# BatteryMonitor-12V-LMT2901.net
KiCad netlist of a schematic drawn in EAGLE
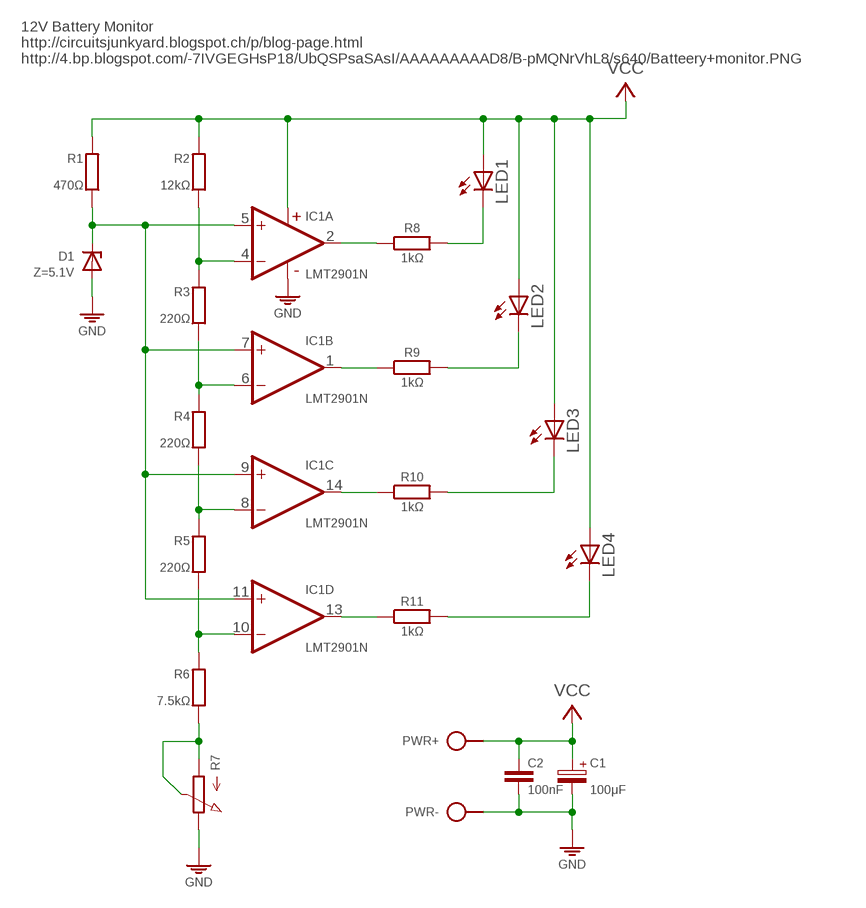
[diagram p0: schematic, sheet 1]

(export (version "E")
  (design (tool "Eeschema 10.0.6"))
  (components
    (comp (ref "C1")
      (value "100μF")
      (footprint "eagle-import:E2,5-4")
      (libsource (lib "eagle-import") (part "CPOLE2,5-4"))
    )
    (comp (ref "C2")
      (value "100nF")
      (footprint "eagle-import:C050-020X044")
      (libsource (lib "eagle-import") (part "C050-020X044"))
    )
    (comp (ref "D1")
      (value "Z=5.1V")
      (footprint "eagle-import:DO34Z5V")
      (libsource (lib "eagle-import") (part "Z-DIODE34Z5V"))
    )
    (comp (ref "IC1")
      (value "LMT2901N")
      (footprint "eagle-import:DIL14")
      (libsource (lib "eagle-import") (part "LMT2901N"))
    )
    (comp (ref "LED1")
      (value "LED3MM")
      (footprint "eagle-import:LED3MM")
      (libsource (lib "eagle-import") (part "LED3MM"))
    )
    (comp (ref "LED2")
      (value "LED3MM")
      (footprint "eagle-import:LED3MM")
      (libsource (lib "eagle-import") (part "LED3MM"))
    )
    (comp (ref "LED3")
      (value "LED3MM")
      (footprint "eagle-import:LED3MM")
      (libsource (lib "eagle-import") (part "LED3MM"))
    )
    (comp (ref "LED4")
      (value "LED3MM")
      (footprint "eagle-import:LED3MM")
      (libsource (lib "eagle-import") (part "LED3MM"))
    )
    (comp (ref "PWR")
      (value "SPAD+-")
      (footprint "eagle-import:SPAD+-")
      (libsource (lib "eagle-import") (part "SPAD+-"))
    )
    (comp (ref "R1")
      (value "470Ω")
      (footprint "eagle-import:0204_10")
      (libsource (lib "eagle-import") (part "R0204/10"))
    )
    (comp (ref "R2")
      (value "12kΩ")
      (footprint "eagle-import:0204_10")
      (libsource (lib "eagle-import") (part "R0204/10"))
    )
    (comp (ref "R3")
      (value "220Ω")
      (footprint "eagle-import:0204_10")
      (libsource (lib "eagle-import") (part "R0204/10"))
    )
    (comp (ref "R4")
      (value "220Ω")
      (footprint "eagle-import:0204_10")
      (libsource (lib "eagle-import") (part "R0204/10"))
    )
    (comp (ref "R5")
      (value "220Ω")
      (footprint "eagle-import:0204_10")
      (libsource (lib "eagle-import") (part "R0204/10"))
    )
    (comp (ref "R6")
      (value "7.5kΩ")
      (footprint "eagle-import:0204_10")
      (libsource (lib "eagle-import") (part "R0204/10"))
    )
    (comp (ref "R7")
      (value "POT")
      (footprint "eagle-import:POT")
      (libsource (lib "eagle-import") (part "POT"))
    )
    (comp (ref "R8")
      (value "1kΩ")
      (footprint "eagle-import:0204_10")
      (libsource (lib "eagle-import") (part "R-H0204/10"))
    )
    (comp (ref "R9")
      (value "1kΩ")
      (footprint "eagle-import:0204_10")
      (libsource (lib "eagle-import") (part "R-H0204/10"))
    )
    (comp (ref "R10")
      (value "1kΩ")
      (footprint "eagle-import:0204_10")
      (libsource (lib "eagle-import") (part "R-H0204/10"))
    )
    (comp (ref "R11")
      (value "1kΩ")
      (footprint "eagle-import:0204_10")
      (libsource (lib "eagle-import") (part "R-H0204/10"))
    )
  )
  (nets
    (net (code "1") (name "GND") (class "Default")
      (node (ref "C1") (pin "-") (pinfunction "-_-") (pintype "passive"))
      (node (ref "C2") (pin "2") (pinfunction "2_2") (pintype "passive"))
      (node (ref "D1") (pin "A") (pinfunction "A_A") (pintype "passive"))
      (node (ref "IC1") (pin "12") (pinfunction "V-_12") (pintype "power_in"))
      (node (ref "PWR") (pin "1") (pinfunction "P$1_1") (pintype "passive"))
      (node (ref "R7") (pin "3") (pinfunction "E_3") (pintype "passive"))
    )
    (net (code "2") (name "Net-(IC1B-+IN)") (class "Default")
      (node (ref "D1") (pin "C") (pinfunction "C_C") (pintype "passive"))
      (node (ref "IC1") (pin "11") (pinfunction "+IN_11") (pintype "input"))
      (node (ref "IC1") (pin "5") (pinfunction "+IN_5") (pintype "input"))
      (node (ref "IC1") (pin "7") (pinfunction "+IN_7") (pintype "input"))
      (node (ref "IC1") (pin "9") (pinfunction "+IN_9") (pintype "input"))
      (node (ref "R1") (pin "1") (pinfunction "1_1") (pintype "passive"))
    )
    (net (code "3") (name "Net-(IC1B--IN)") (class "Default")
      (node (ref "IC1") (pin "4") (pinfunction "-IN_4") (pintype "input"))
      (node (ref "R2") (pin "1") (pinfunction "1_1") (pintype "passive"))
      (node (ref "R3") (pin "2") (pinfunction "2_2") (pintype "passive"))
    )
    (net (code "4") (name "Net-(IC1B-OUT)") (class "Default")
      (node (ref "IC1") (pin "2") (pinfunction "OUT_2") (pintype "output"))
      (node (ref "R8") (pin "1") (pinfunction "1_1") (pintype "passive"))
    )
    (net (code "5") (name "Net-(IC1C--IN)") (class "Default")
      (node (ref "IC1") (pin "6") (pinfunction "-IN_6") (pintype "input"))
      (node (ref "R3") (pin "1") (pinfunction "1_1") (pintype "passive"))
      (node (ref "R4") (pin "2") (pinfunction "2_2") (pintype "passive"))
    )
    (net (code "6") (name "Net-(IC1C-OUT)") (class "Default")
      (node (ref "IC1") (pin "1") (pinfunction "OUT_1") (pintype "output"))
      (node (ref "R9") (pin "1") (pinfunction "1_1") (pintype "passive"))
    )
    (net (code "7") (name "Net-(IC1D--IN)") (class "Default")
      (node (ref "IC1") (pin "8") (pinfunction "-IN_8") (pintype "input"))
      (node (ref "R4") (pin "1") (pinfunction "1_1") (pintype "passive"))
      (node (ref "R5") (pin "2") (pinfunction "2_2") (pintype "passive"))
    )
    (net (code "8") (name "Net-(IC1D-OUT)") (class "Default")
      (node (ref "IC1") (pin "14") (pinfunction "OUT_14") (pintype "output"))
      (node (ref "R10") (pin "1") (pinfunction "1_1") (pintype "passive"))
    )
    (net (code "9") (name "Net-(IC1E--IN)") (class "Default")
      (node (ref "IC1") (pin "10") (pinfunction "-IN_10") (pintype "input"))
      (node (ref "R5") (pin "1") (pinfunction "1_1") (pintype "passive"))
      (node (ref "R6") (pin "2") (pinfunction "2_2") (pintype "passive"))
    )
    (net (code "10") (name "Net-(IC1E-OUT)") (class "Default")
      (node (ref "IC1") (pin "13") (pinfunction "OUT_13") (pintype "output"))
      (node (ref "R11") (pin "1") (pinfunction "1_1") (pintype "passive"))
    )
    (net (code "11") (name "Net-(LED1-C)") (class "Default")
      (node (ref "LED1") (pin "K") (pinfunction "C_K") (pintype "passive"))
      (node (ref "R8") (pin "2") (pinfunction "2_2") (pintype "passive"))
    )
    (net (code "12") (name "Net-(LED2-C)") (class "Default")
      (node (ref "LED2") (pin "K") (pinfunction "C_K") (pintype "passive"))
      (node (ref "R9") (pin "2") (pinfunction "2_2") (pintype "passive"))
    )
    (net (code "13") (name "Net-(LED3-C)") (class "Default")
      (node (ref "LED3") (pin "K") (pinfunction "C_K") (pintype "passive"))
      (node (ref "R10") (pin "2") (pinfunction "2_2") (pintype "passive"))
    )
    (net (code "14") (name "Net-(LED4-C)") (class "Default")
      (node (ref "LED4") (pin "K") (pinfunction "C_K") (pintype "passive"))
      (node (ref "R11") (pin "2") (pinfunction "2_2") (pintype "passive"))
    )
    (net (code "15") (name "Net-(R7-A)") (class "Default")
      (node (ref "R6") (pin "1") (pinfunction "1_1") (pintype "passive"))
      (node (ref "R7") (pin "1") (pinfunction "A_1") (pintype "passive"))
      (node (ref "R7") (pin "2") (pinfunction "S_2") (pintype "passive"))
    )
    (net (code "16") (name "VCC") (class "Default")
      (node (ref "C1") (pin "+") (pinfunction "+_+") (pintype "passive"))
      (node (ref "C2") (pin "1") (pinfunction "1_1") (pintype "passive"))
      (node (ref "IC1") (pin "3") (pinfunction "V+_3") (pintype "power_in"))
      (node (ref "LED1") (pin "A") (pinfunction "A_A") (pintype "passive"))
      (node (ref "LED2") (pin "A") (pinfunction "A_A") (pintype "passive"))
      (node (ref "LED3") (pin "A") (pinfunction "A_A") (pintype "passive"))
      (node (ref "LED4") (pin "A") (pinfunction "A_A") (pintype "passive"))
      (node (ref "PWR") (pin "2") (pinfunction "P$1_2") (pintype "passive"))
      (node (ref "R1") (pin "2") (pinfunction "2_2") (pintype "passive"))
      (node (ref "R2") (pin "2") (pinfunction "2_2") (pintype "passive"))
    )
  )
)
